# HC-06.net
KiCad netlist of a schematic drawn in Altium Designer
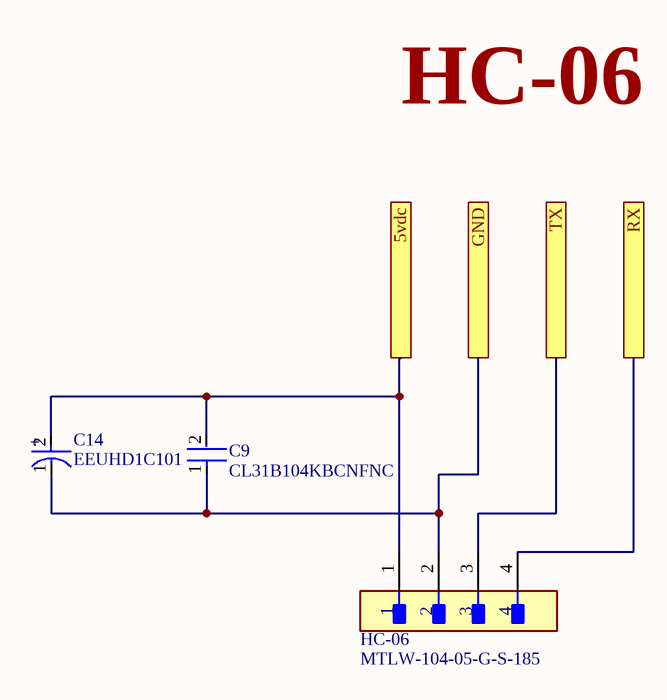
[diagram p0: HC-06.SchDoc]

(export (version "E")
  (design (tool "Eeschema 10.0.6"))
  (components
    (comp (ref "C9")
      (value "CL31B104KBCNFNC")
      (footprint "FP-CL31-IPC_C")
      (description "Cap Ceramic 100nF 50V X7R ±10% SMD 1206 +125°C Embossed T/R")
      (fields (field (name "TOLERANCE") "10%"))
      (libsource (lib "Altium Content Vault") (part "b4654b650e69147ec39a6b967a45e02"))
    )
    (comp (ref "C14")
      (value "EEUHD1C101")
      (footprint "FP-RAD-TH-D_5_0_5-L_11_1-MFG")
      (description "Aluminum Electrolytic Capacitors (Radial Lead Type) AEC-Q200 Qualified 100uF ±20% 16V")
      (fields (field (name "TOLERANCE") "20%") (field (name "VOLTAGE") "16V"))
      (libsource (lib "Altium Content Vault") (part "a00bbbee19879c290e62620ae7e47b1"))
    )
    (comp (ref "HC-06")
      (value "MTLW-104-05-G-S-185")
      (footprint "FP-MTLW-104-05-G-S-185-MFG")
      (description "CONN HEADER VERT 4POS 2.54MM")
      (libsource (lib "Altium Content Vault") (part "299a8cea1bdcbc3624fe62c390fa72c"))
    )
  )
  (nets
    (net (code "1") (name "/5vdc") (class "Default")
      (node (ref "C14") (pin "2") (pinfunction "A_2") (pintype "passive"))
      (node (ref "C9") (pin "2") (pinfunction "2_2") (pintype "passive"))
      (node (ref "HC-06") (pin "1") (pinfunction "1_1") (pintype "passive"))
    )
    (net (code "2") (name "/GND") (class "Default")
      (node (ref "C14") (pin "1") (pinfunction "C_1") (pintype "passive"))
      (node (ref "C9") (pin "1") (pinfunction "1_1") (pintype "passive"))
      (node (ref "HC-06") (pin "2") (pinfunction "2_2") (pintype "passive"))
    )
    (net (code "3") (name "/RX") (class "Default")
      (node (ref "HC-06") (pin "4") (pinfunction "4_4") (pintype "passive"))
    )
    (net (code "4") (name "/TX") (class "Default")
      (node (ref "HC-06") (pin "3") (pinfunction "3_3") (pintype "passive"))
    )
  )
)
